# Sheet1.net
KiCad netlist of a schematic drawn in Altium Designer
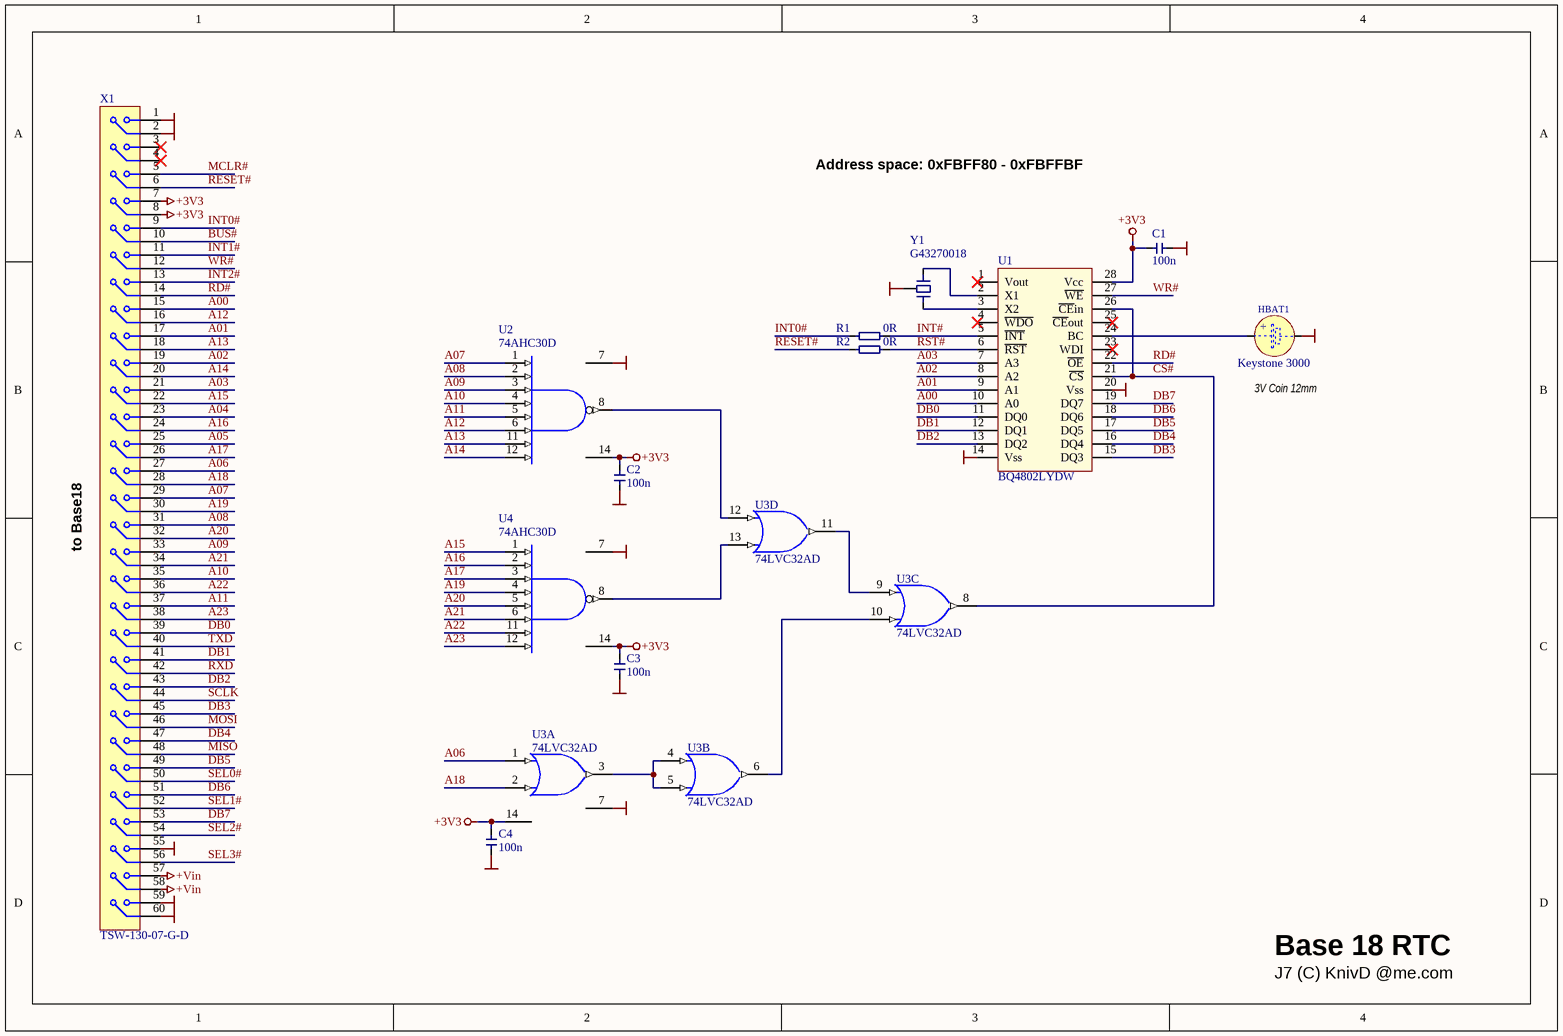
[diagram p0: Sheet1.SchDoc]

(export (version "E")
  (design (tool "Eeschema 10.0.6"))
  (components
    (comp (ref "C1")
      (value "100n")
      (footprint "CAPC3216X110N")
      (description "Capacitor")
      (libsource (lib "Discretes") (part "Capacitor"))
    )
    (comp (ref "C2")
      (value "100n")
      (footprint "CAPC3216X110N")
      (description "Capacitor")
      (libsource (lib "Discretes") (part "Capacitor"))
    )
    (comp (ref "C3")
      (value "100n")
      (footprint "CAPC3216X110N")
      (description "Capacitor")
      (libsource (lib "Discretes") (part "Capacitor"))
    )
    (comp (ref "C4")
      (value "100n")
      (footprint "CAPC3216X110N")
      (description "Capacitor")
      (libsource (lib "Discretes") (part "Capacitor"))
    )
    (comp (ref "HBAT1")
      (value "Keystone 3000")
      (footprint "BATH_KEYSTONE_3000")
      (description "Battery Holder whit 2 Pin")
      (fields
        (field (name "PART NUMBER") "BATH_KEYSTONE_3000")
        (field (name "MANUFACTURER") "KEYSTONE")
        (field (name "AUTHOR") "CERN DEM JLC")
      )
      (libsource (lib "Eletro-mechanical") (part "Battery Holder 2 Pin"))
    )
    (comp (ref "R1")
      (value "0R")
      (footprint "RESC3216X75N")
      (description "Resistor")
      (libsource (lib "Discretes") (part "Resistor"))
    )
    (comp (ref "R2")
      (value "0R")
      (footprint "RESC3216X75N")
      (description "Resistor")
      (libsource (lib "Discretes") (part "Resistor"))
    )
    (comp (ref "U1")
      (value "BQ4802LYDW")
      (footprint "SOIC127P1032X265-28N")
      (description "PARALLEL REAL-TIME CLOCK WITH CPU SUPERVISOR AND  EXTERNAL SRAM NONVOLATILE MEMORY BACKUP")
      (fields (field (name "MANUFACTURER") "Texas Instruments"))
      (libsource (lib "IC Other Functions") (part "BQ4802LY"))
    )
    (comp (ref "U2")
      (value "74AHC30D")
      (footprint "SOIC14")
      (description "8-Input NAND Gate")
      (fields
        (field (name "PART NUMBER") "74HCT30N")
        (field (name "MANUFACTURER") "NXP SEMICONDUCTORS")
        (field (name "AUTHOR") "CERN DEM JLC")
      )
      (libsource (lib "ICs And Semiconductors") (part "7430"))
    )
    (comp (ref "U3")
      (value "74LVC32AD")
      (footprint "SOIC14")
      (description "Quad 2-Input OR Gate")
      (fields
        (field (name "PART NUMBER") "74HCT32N")
        (field (name "MANUFACTURER") "NXP SEMICONDUCTORS")
        (field (name "AUTHOR") "CERN DEM JLC")
      )
      (libsource (lib "ICs And Semiconductors") (part "7432"))
    )
    (comp (ref "U4")
      (value "74AHC30D")
      (footprint "SOIC14")
      (description "8-Input NAND Gate")
      (fields
        (field (name "PART NUMBER") "74HCT30N")
        (field (name "MANUFACTURER") "NXP SEMICONDUCTORS")
        (field (name "AUTHOR") "CERN DEM JLC")
      )
      (libsource (lib "ICs And Semiconductors") (part "7430"))
    )
    (comp (ref "X1")
      (value "TSW-130-07-G-D")
      (footprint "DIL60-M-EDGE")
      (description "Dual row, 60-way connector")
      (libsource (lib "Connectors") (part "Connector 2x30"))
    )
    (comp (ref "Y1")
      (value "G43270018")
      (footprint "Crystal 79X37 (4)")
      (description "Crystal Resonator")
      (libsource (lib "Discretes") (part "Crystal (ground)"))
    )
  )
  (nets
    (net (code "1") (name "+3V3") (class "Default")
      (node (ref "C1") (pin "1") (pintype "passive"))
      (node (ref "C2") (pin "2") (pintype "passive"))
      (node (ref "C3") (pin "2") (pintype "passive"))
      (node (ref "C4") (pin "2") (pintype "passive"))
      (node (ref "U1") (pin "28") (pinfunction "Vcc_28") (pintype "passive"))
      (node (ref "U2") (pin "14") (pinfunction "VCC_14") (pintype "power_in"))
      (node (ref "U3") (pin "14") (pinfunction "VCC_14") (pintype "power_in"))
      (node (ref "U4") (pin "14") (pinfunction "VCC_14") (pintype "power_in"))
      (node (ref "X1") (pin "7") (pinfunction "7_7") (pintype "passive"))
      (node (ref "X1") (pin "8") (pinfunction "8_8") (pintype "passive"))
    )
    (net (code "2") (name "+Vin") (class "Default")
      (node (ref "X1") (pin "57") (pinfunction "57_57") (pintype "passive"))
      (node (ref "X1") (pin "58") (pinfunction "58_58") (pintype "passive"))
    )
    (net (code "3") (name "/A00") (class "Default")
      (node (ref "U1") (pin "10") (pinfunction "A0_10") (pintype "passive"))
      (node (ref "X1") (pin "15") (pinfunction "15_15") (pintype "passive"))
    )
    (net (code "4") (name "/A01") (class "Default")
      (node (ref "U1") (pin "9") (pinfunction "A1_9") (pintype "passive"))
      (node (ref "X1") (pin "17") (pinfunction "17_17") (pintype "passive"))
    )
    (net (code "5") (name "/A02") (class "Default")
      (node (ref "U1") (pin "8") (pinfunction "A2_8") (pintype "passive"))
      (node (ref "X1") (pin "19") (pinfunction "19_19") (pintype "passive"))
    )
    (net (code "6") (name "/A03") (class "Default")
      (node (ref "U1") (pin "7") (pinfunction "A3_7") (pintype "passive"))
      (node (ref "X1") (pin "21") (pinfunction "21_21") (pintype "passive"))
    )
    (net (code "7") (name "/A04") (class "Default")
      (node (ref "X1") (pin "23") (pinfunction "23_23") (pintype "passive"))
    )
    (net (code "8") (name "/A05") (class "Default")
      (node (ref "X1") (pin "25") (pinfunction "25_25") (pintype "passive"))
    )
    (net (code "9") (name "/A06") (class "Default")
      (node (ref "U3") (pin "1") (pintype "input"))
      (node (ref "X1") (pin "27") (pinfunction "27_27") (pintype "passive"))
    )
    (net (code "10") (name "/A07") (class "Default")
      (node (ref "U2") (pin "1") (pintype "input"))
      (node (ref "X1") (pin "29") (pinfunction "29_29") (pintype "passive"))
    )
    (net (code "11") (name "/A08") (class "Default")
      (node (ref "U2") (pin "2") (pintype "input"))
      (node (ref "X1") (pin "31") (pinfunction "31_31") (pintype "passive"))
    )
    (net (code "12") (name "/A09") (class "Default")
      (node (ref "U2") (pin "3") (pintype "input"))
      (node (ref "X1") (pin "33") (pinfunction "33_33") (pintype "passive"))
    )
    (net (code "13") (name "/A10") (class "Default")
      (node (ref "U2") (pin "4") (pintype "input"))
      (node (ref "X1") (pin "35") (pinfunction "35_35") (pintype "passive"))
    )
    (net (code "14") (name "/A11") (class "Default")
      (node (ref "U2") (pin "5") (pintype "input"))
      (node (ref "X1") (pin "37") (pinfunction "37_37") (pintype "passive"))
    )
    (net (code "15") (name "/A12") (class "Default")
      (node (ref "U2") (pin "6") (pintype "input"))
      (node (ref "X1") (pin "16") (pinfunction "16_16") (pintype "passive"))
    )
    (net (code "16") (name "/A13") (class "Default")
      (node (ref "U2") (pin "11") (pintype "input"))
      (node (ref "X1") (pin "18") (pinfunction "18_18") (pintype "passive"))
    )
    (net (code "17") (name "/A14") (class "Default")
      (node (ref "U2") (pin "12") (pintype "input"))
      (node (ref "X1") (pin "20") (pinfunction "20_20") (pintype "passive"))
    )
    (net (code "18") (name "/A15") (class "Default")
      (node (ref "U4") (pin "1") (pintype "input"))
      (node (ref "X1") (pin "22") (pinfunction "22_22") (pintype "passive"))
    )
    (net (code "19") (name "/A16") (class "Default")
      (node (ref "U4") (pin "2") (pintype "input"))
      (node (ref "X1") (pin "24") (pinfunction "24_24") (pintype "passive"))
    )
    (net (code "20") (name "/A17") (class "Default")
      (node (ref "U4") (pin "3") (pintype "input"))
      (node (ref "X1") (pin "26") (pinfunction "26_26") (pintype "passive"))
    )
    (net (code "21") (name "/A18") (class "Default")
      (node (ref "U3") (pin "2") (pintype "input"))
      (node (ref "X1") (pin "28") (pinfunction "28_28") (pintype "passive"))
    )
    (net (code "22") (name "/A19") (class "Default")
      (node (ref "U4") (pin "4") (pintype "input"))
      (node (ref "X1") (pin "30") (pinfunction "30_30") (pintype "passive"))
    )
    (net (code "23") (name "/A20") (class "Default")
      (node (ref "U4") (pin "5") (pintype "input"))
      (node (ref "X1") (pin "32") (pinfunction "32_32") (pintype "passive"))
    )
    (net (code "24") (name "/A21") (class "Default")
      (node (ref "U4") (pin "6") (pintype "input"))
      (node (ref "X1") (pin "34") (pinfunction "34_34") (pintype "passive"))
    )
    (net (code "25") (name "/A22") (class "Default")
      (node (ref "U4") (pin "11") (pintype "input"))
      (node (ref "X1") (pin "36") (pinfunction "36_36") (pintype "passive"))
    )
    (net (code "26") (name "/A23") (class "Default")
      (node (ref "U4") (pin "12") (pintype "input"))
      (node (ref "X1") (pin "38") (pinfunction "38_38") (pintype "passive"))
    )
    (net (code "27") (name "/BUS#") (class "Default")
      (node (ref "X1") (pin "10") (pinfunction "10_10") (pintype "passive"))
    )
    (net (code "28") (name "/CS#") (class "Default")
      (node (ref "U1") (pin "21") (pinfunction "~{CS}_21") (pintype "passive"))
      (node (ref "U1") (pin "26") (pinfunction "~{CE}in_26") (pintype "passive"))
      (node (ref "U3") (pin "8") (pinfunction "Y_8") (pintype "output"))
    )
    (net (code "29") (name "/DB0") (class "Default")
      (node (ref "U1") (pin "11") (pinfunction "DQ0_11") (pintype "passive"))
      (node (ref "X1") (pin "39") (pinfunction "39_39") (pintype "passive"))
    )
    (net (code "30") (name "/DB1") (class "Default")
      (node (ref "U1") (pin "12") (pinfunction "DQ1_12") (pintype "passive"))
      (node (ref "X1") (pin "41") (pinfunction "41_41") (pintype "passive"))
    )
    (net (code "31") (name "/DB2") (class "Default")
      (node (ref "U1") (pin "13") (pinfunction "DQ2_13") (pintype "passive"))
      (node (ref "X1") (pin "43") (pinfunction "43_43") (pintype "passive"))
    )
    (net (code "32") (name "/DB3") (class "Default")
      (node (ref "U1") (pin "15") (pinfunction "DQ3_15") (pintype "passive"))
      (node (ref "X1") (pin "45") (pinfunction "45_45") (pintype "passive"))
    )
    (net (code "33") (name "/DB4") (class "Default")
      (node (ref "U1") (pin "16") (pinfunction "DQ4_16") (pintype "passive"))
      (node (ref "X1") (pin "47") (pinfunction "47_47") (pintype "passive"))
    )
    (net (code "34") (name "/DB5") (class "Default")
      (node (ref "U1") (pin "17") (pinfunction "DQ5_17") (pintype "passive"))
      (node (ref "X1") (pin "49") (pinfunction "49_49") (pintype "passive"))
    )
    (net (code "35") (name "/DB6") (class "Default")
      (node (ref "U1") (pin "18") (pinfunction "DQ6_18") (pintype "passive"))
      (node (ref "X1") (pin "51") (pinfunction "51_51") (pintype "passive"))
    )
    (net (code "36") (name "/DB7") (class "Default")
      (node (ref "U1") (pin "19") (pinfunction "DQ7_19") (pintype "passive"))
      (node (ref "X1") (pin "53") (pinfunction "53_53") (pintype "passive"))
    )
    (net (code "37") (name "/INT#") (class "Default")
      (node (ref "R1") (pin "2") (pintype "passive"))
      (node (ref "U1") (pin "5") (pinfunction "~{INT}_5") (pintype "passive"))
    )
    (net (code "38") (name "/INT0#") (class "Default")
      (node (ref "R1") (pin "1") (pintype "passive"))
      (node (ref "X1") (pin "9") (pinfunction "9_9") (pintype "passive"))
    )
    (net (code "39") (name "/INT1#") (class "Default")
      (node (ref "X1") (pin "11") (pinfunction "11_11") (pintype "passive"))
    )
    (net (code "40") (name "/INT2#") (class "Default")
      (node (ref "X1") (pin "13") (pinfunction "13_13") (pintype "passive"))
    )
    (net (code "41") (name "/MCLR#") (class "Default")
      (node (ref "X1") (pin "5") (pinfunction "5_5") (pintype "passive"))
    )
    (net (code "42") (name "/MISO") (class "Default")
      (node (ref "X1") (pin "48") (pinfunction "48_48") (pintype "passive"))
    )
    (net (code "43") (name "/MOSI") (class "Default")
      (node (ref "X1") (pin "46") (pinfunction "46_46") (pintype "passive"))
    )
    (net (code "44") (name "/RD#") (class "Default")
      (node (ref "U1") (pin "22") (pinfunction "~{OE}_22") (pintype "passive"))
      (node (ref "X1") (pin "14") (pinfunction "14_14") (pintype "passive"))
    )
    (net (code "45") (name "/RESET#") (class "Default")
      (node (ref "R2") (pin "1") (pintype "passive"))
      (node (ref "X1") (pin "6") (pinfunction "6_6") (pintype "passive"))
    )
    (net (code "46") (name "/RST#") (class "Default")
      (node (ref "R2") (pin "2") (pintype "passive"))
      (node (ref "U1") (pin "6") (pinfunction "~{RST}_6") (pintype "passive"))
    )
    (net (code "47") (name "/RXD") (class "Default")
      (node (ref "X1") (pin "42") (pinfunction "42_42") (pintype "passive"))
    )
    (net (code "48") (name "/SCLK") (class "Default")
      (node (ref "X1") (pin "44") (pinfunction "44_44") (pintype "passive"))
    )
    (net (code "49") (name "/SEL0#") (class "Default")
      (node (ref "X1") (pin "50") (pinfunction "50_50") (pintype "passive"))
    )
    (net (code "50") (name "/SEL1#") (class "Default")
      (node (ref "X1") (pin "52") (pinfunction "52_52") (pintype "passive"))
    )
    (net (code "51") (name "/SEL2#") (class "Default")
      (node (ref "X1") (pin "54") (pinfunction "54_54") (pintype "passive"))
    )
    (net (code "52") (name "/SEL3#") (class "Default")
      (node (ref "X1") (pin "56") (pinfunction "56_56") (pintype "passive"))
    )
    (net (code "53") (name "/TXD") (class "Default")
      (node (ref "X1") (pin "40") (pinfunction "40_40") (pintype "passive"))
    )
    (net (code "54") (name "/WR#") (class "Default")
      (node (ref "U1") (pin "27") (pinfunction "~{WE}_27") (pintype "passive"))
      (node (ref "X1") (pin "12") (pinfunction "12_12") (pintype "passive"))
    )
    (net (code "55") (name "GND") (class "Default")
      (node (ref "C1") (pin "2") (pintype "passive"))
      (node (ref "C2") (pin "1") (pintype "passive"))
      (node (ref "C3") (pin "1") (pintype "passive"))
      (node (ref "C4") (pin "1") (pintype "passive"))
      (node (ref "HBAT1") (pin "2") (pinfunction "MINUS_2") (pintype "power_in"))
      (node (ref "U1") (pin "14") (pinfunction "Vss_14") (pintype "passive"))
      (node (ref "U1") (pin "20") (pinfunction "Vss_20") (pintype "passive"))
      (node (ref "U2") (pin "7") (pinfunction "GND_7") (pintype "power_in"))
      (node (ref "U3") (pin "7") (pinfunction "GND_7") (pintype "power_in"))
      (node (ref "U4") (pin "7") (pinfunction "GND_7") (pintype "power_in"))
      (node (ref "X1") (pin "1") (pinfunction "1_1") (pintype "passive"))
      (node (ref "X1") (pin "2") (pinfunction "2_2") (pintype "passive"))
      (node (ref "X1") (pin "55") (pinfunction "55_55") (pintype "passive"))
      (node (ref "X1") (pin "59") (pinfunction "59_59") (pintype "passive"))
      (node (ref "X1") (pin "60") (pinfunction "60_60") (pintype "passive"))
      (node (ref "Y1") (pin "0") (pinfunction "GND_0") (pintype "passive"))
    )
    (net (code "56") (name "Net-(HBAT1-PLUS)") (class "Default")
      (node (ref "HBAT1") (pin "1") (pinfunction "PLUS_1") (pintype "power_in"))
      (node (ref "U1") (pin "24") (pinfunction "BC_24") (pintype "passive"))
    )
    (net (code "57") (name "Net-(U1-X1)") (class "Default")
      (node (ref "U1") (pin "2") (pinfunction "X1_2") (pintype "passive"))
      (node (ref "Y1") (pin "1") (pintype "passive"))
    )
    (net (code "58") (name "Net-(U1-X2)") (class "Default")
      (node (ref "U1") (pin "3") (pinfunction "X2_3") (pintype "passive"))
      (node (ref "Y1") (pin "2") (pintype "passive"))
    )
    (net (code "59") (name "Net-(U3B-A)") (class "Default")
      (node (ref "U3") (pin "3") (pintype "output"))
      (node (ref "U3") (pin "4") (pinfunction "A_4") (pintype "input"))
      (node (ref "U3") (pin "5") (pinfunction "B_5") (pintype "input"))
    )
    (net (code "60") (name "Net-(U3B-Y)") (class "Default")
      (node (ref "U3") (pin "10") (pinfunction "B_10") (pintype "input"))
      (node (ref "U3") (pin "6") (pinfunction "Y_6") (pintype "output"))
    )
    (net (code "61") (name "Net-(U3C-A)") (class "Default")
      (node (ref "U3") (pin "11") (pinfunction "Y_11") (pintype "output"))
      (node (ref "U3") (pin "9") (pinfunction "A_9") (pintype "input"))
    )
    (net (code "62") (name "Net-(U3D-A)") (class "Default")
      (node (ref "U2") (pin "8") (pintype "output"))
      (node (ref "U3") (pin "12") (pinfunction "A_12") (pintype "input"))
    )
    (net (code "63") (name "Net-(U3D-B)") (class "Default")
      (node (ref "U3") (pin "13") (pinfunction "B_13") (pintype "input"))
      (node (ref "U4") (pin "8") (pintype "output"))
    )
    (net (code "64") (name "unconnected-(U1-Vout-Pad1)") (class "Default")
      (node (ref "U1") (pin "1") (pinfunction "Vout_1") (pintype "passive+no_connect"))
    )
    (net (code "65") (name "unconnected-(U1-WDI-Pad23)") (class "Default")
      (node (ref "U1") (pin "23") (pinfunction "WDI_23") (pintype "passive+no_connect"))
    )
    (net (code "66") (name "unconnected-(U1-~{CE}out-Pad25)") (class "Default")
      (node (ref "U1") (pin "25") (pinfunction "~{CE}out_25") (pintype "passive+no_connect"))
    )
    (net (code "67") (name "unconnected-(U1-~{WDO}-Pad4)") (class "Default")
      (node (ref "U1") (pin "4") (pinfunction "~{WDO}_4") (pintype "passive+no_connect"))
    )
    (net (code "68") (name "unconnected-(X1-Pad3)") (class "Default")
      (node (ref "X1") (pin "3") (pinfunction "3_3") (pintype "passive+no_connect"))
    )
    (net (code "69") (name "unconnected-(X1-Pad4)") (class "Default")
      (node (ref "X1") (pin "4") (pinfunction "4_4") (pintype "passive+no_connect"))
    )
  )
)
